# SCH_d_02_e_00.net
KiCad netlist of a schematic drawn in EasyEDA
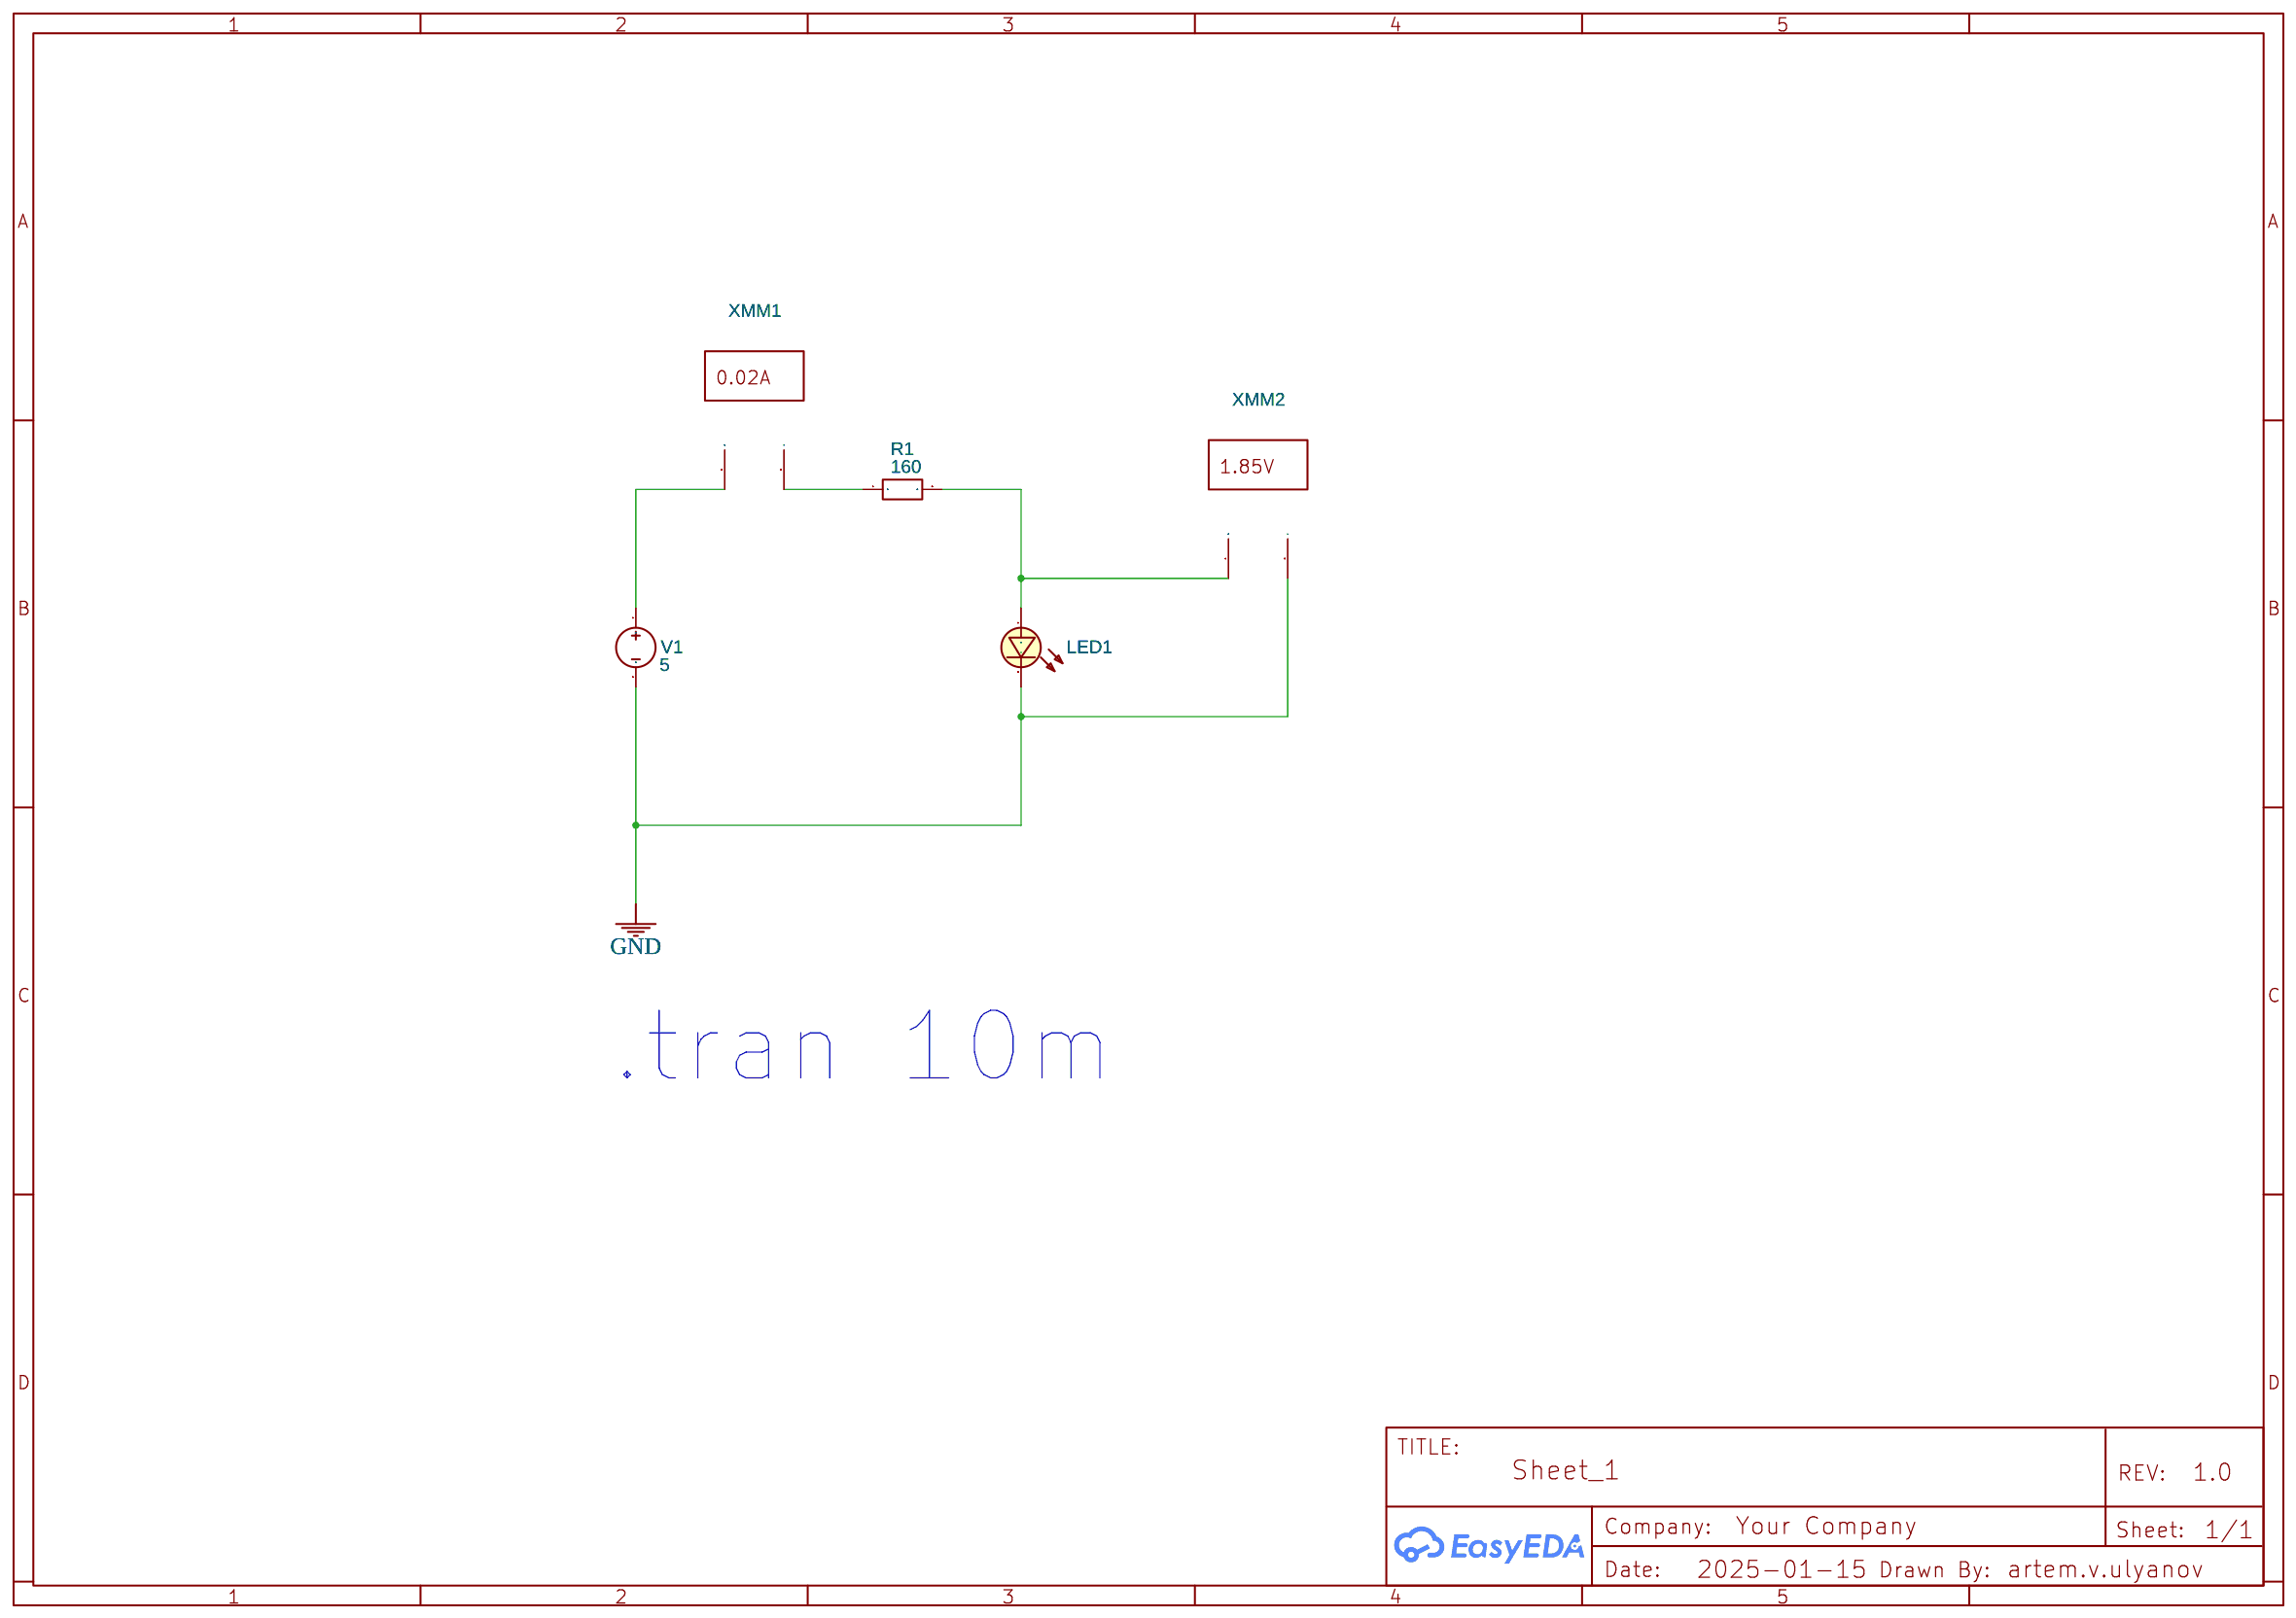
[diagram p0: schematic sheet]

(export (version "E")
  (design (tool "Eeschema 10.0.6"))
  (components
    (comp (ref "LED1") (value "LED") (libsource (lib "") (part "LED")))
    (comp (ref "R1") (value "160") (libsource (lib "") (part "R_0603_EU")))
    (comp (ref "V1") (value "5") (libsource (lib "") (part "VDC")))
    (comp (ref "XMM1") (value "Multimeter") (libsource (lib "") (part "MULTIMETER_1")))
    (comp (ref "XMM2") (value "Multimeter") (libsource (lib "") (part "MULTIMETER")))
  )
  (nets
    (net (code "1") (name "GND") (class "Default")
      (node (ref "LED1") (pin "2") (pinfunction "-_2") (pintype "unspecified"))
      (node (ref "V1") (pin "2") (pinfunction "2_2") (pintype "unspecified"))
      (node (ref "XMM2") (pin "2") (pinfunction "I_2") (pintype "unspecified"))
    )
    (net (code "2") (name "Net-(LED1-+)") (class "Default")
      (node (ref "LED1") (pin "1") (pinfunction "+_1") (pintype "unspecified"))
      (node (ref "R1") (pin "2") (pinfunction "2_2") (pintype "unspecified"))
      (node (ref "XMM2") (pin "1") (pinfunction "+_1") (pintype "unspecified"))
    )
    (net (code "3") (name "Net-(XMM1-+)") (class "Default")
      (node (ref "V1") (pin "1") (pinfunction "1_1") (pintype "unspecified"))
      (node (ref "XMM1") (pin "1") (pinfunction "+_1") (pintype "unspecified"))
    )
    (net (code "4") (name "Net-(XMM1-I)") (class "Default")
      (node (ref "R1") (pin "1") (pinfunction "1_1") (pintype "unspecified"))
      (node (ref "XMM1") (pin "2") (pinfunction "I_2") (pintype "unspecified"))
    )
  )
)
